# eFingernailAllComponents.net
KiCad netlist of a schematic drawn in EAGLE
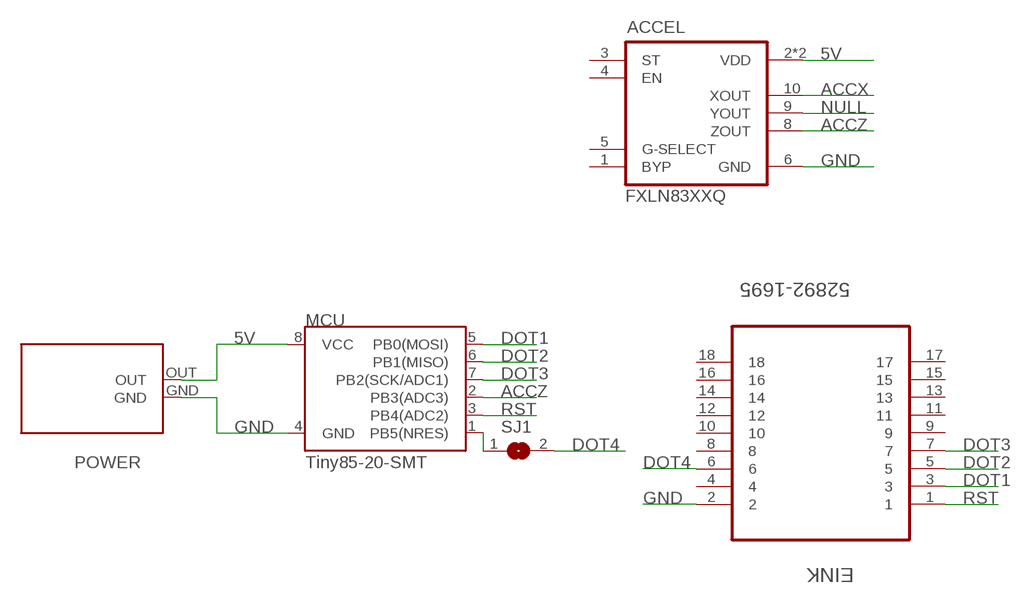
[diagram p0: schematic, sheet 1]

(export (version "E")
  (design (tool "Eeschema 10.0.6"))
  (components
    (comp (ref "ACCEL")
      (value "FXLN83XXQ")
      (footprint "eagle-import:QFN12-3X3")
      (libsource (lib "eagle-import") (part "FXLN83XXQ"))
    )
    (comp (ref "EINK")
      (value "52892-1695")
      (footprint "eagle-import:MOLEX_52892-1695")
      (libsource (lib "eagle-import") (part "52892-1695"))
    )
    (comp (ref "MCU")
      (value "Tiny85-20-SMT")
      (footprint "eagle-import:SO08-EIAJ")
      (libsource (lib "eagle-import") (part "ATTINY45TINY85-20-SMT"))
    )
    (comp (ref "POWER")
      (value "P9027LP-R")
      (footprint "eagle-import:P9027LP-R")
      (libsource (lib "eagle-import") (part "P9027LP-R"))
    )
    (comp (ref "SJ1")
      (value "SOLDERJUMPER")
      (footprint "eagle-import:SOLDERJUMPER_ARROW_NOPASTE")
      (libsource (lib "eagle-import") (part "SOLDERJUMPER"))
    )
  )
  (nets
    (net (code "1") (name "/5V") (class "Default")
      (node (ref "ACCEL") (pin "2") (pinfunction "VDD_2") (pintype "power_in"))
      (node (ref "ACCEL") (pin "7") (pinfunction "VDD_7") (pintype "power_in"))
      (node (ref "MCU") (pin "8") (pinfunction "VCC_8") (pintype "bidirectional"))
      (node (ref "POWER") (pin "OUT") (pinfunction "OUT_OUT") (pintype "power_in"))
    )
    (net (code "2") (name "/ACCX") (class "Default")
      (node (ref "ACCEL") (pin "10") (pinfunction "XOUT_10") (pintype "output"))
    )
    (net (code "3") (name "/ACCZ") (class "Default")
      (node (ref "ACCEL") (pin "8") (pinfunction "ZOUT_8") (pintype "output"))
      (node (ref "MCU") (pin "2") (pinfunction "PB3(ADC3)_2") (pintype "bidirectional"))
    )
    (net (code "4") (name "/DOT1") (class "Default")
      (node (ref "EINK") (pin "3") (pinfunction "3_3") (pintype "passive"))
      (node (ref "MCU") (pin "5") (pinfunction "PB0(MOSI)_5") (pintype "bidirectional"))
    )
    (net (code "5") (name "/DOT2") (class "Default")
      (node (ref "EINK") (pin "5") (pinfunction "5_5") (pintype "passive"))
      (node (ref "MCU") (pin "6") (pinfunction "PB1(MISO)_6") (pintype "bidirectional"))
    )
    (net (code "6") (name "/DOT3") (class "Default")
      (node (ref "EINK") (pin "7") (pinfunction "7_7") (pintype "passive"))
      (node (ref "MCU") (pin "7") (pinfunction "PB2(SCK/ADC1)_7") (pintype "bidirectional"))
    )
    (net (code "7") (name "/DOT4") (class "Default")
      (node (ref "EINK") (pin "6") (pinfunction "6_6") (pintype "passive"))
      (node (ref "SJ1") (pin "2") (pinfunction "2_2") (pintype "passive"))
    )
    (net (code "8") (name "/GND") (class "Default")
      (node (ref "ACCEL") (pin "6") (pinfunction "GND_6") (pintype "power_in"))
      (node (ref "EINK") (pin "2") (pinfunction "2_2") (pintype "passive"))
      (node (ref "MCU") (pin "4") (pinfunction "GND_4") (pintype "bidirectional"))
      (node (ref "POWER") (pin "GND") (pinfunction "GND_GND") (pintype "power_in"))
    )
    (net (code "9") (name "/NULL") (class "Default")
      (node (ref "ACCEL") (pin "9") (pinfunction "YOUT_9") (pintype "output"))
    )
    (net (code "10") (name "/RST") (class "Default")
      (node (ref "EINK") (pin "1") (pinfunction "1_1") (pintype "passive"))
      (node (ref "MCU") (pin "3") (pinfunction "PB4(ADC2)_3") (pintype "bidirectional"))
    )
    (net (code "11") (name "Net-(MCU-PB5(NRES))") (class "Default")
      (node (ref "MCU") (pin "1") (pinfunction "PB5(NRES)_1") (pintype "bidirectional"))
      (node (ref "SJ1") (pin "1") (pinfunction "1_1") (pintype "passive"))
    )
    (net (code "12") (name "unconnected-(ACCEL-BYP-Pad1)") (class "Default")
      (node (ref "ACCEL") (pin "1") (pinfunction "BYP_1") (pintype "bidirectional"))
    )
    (net (code "13") (name "unconnected-(ACCEL-EN-Pad4)") (class "Default")
      (node (ref "ACCEL") (pin "4") (pinfunction "EN_4") (pintype "bidirectional"))
    )
    (net (code "14") (name "unconnected-(ACCEL-G-SELECT-Pad5)") (class "Default")
      (node (ref "ACCEL") (pin "5") (pinfunction "G-SELECT_5") (pintype "bidirectional"))
    )
    (net (code "15") (name "unconnected-(ACCEL-ST-Pad3)") (class "Default")
      (node (ref "ACCEL") (pin "3") (pinfunction "ST_3") (pintype "bidirectional"))
    )
    (net (code "16") (name "unconnected-(EINK-Pad4)") (class "Default")
      (node (ref "EINK") (pin "4") (pinfunction "4_4") (pintype "passive"))
    )
    (net (code "17") (name "unconnected-(EINK-Pad8)") (class "Default")
      (node (ref "EINK") (pin "8") (pinfunction "8_8") (pintype "passive"))
    )
    (net (code "18") (name "unconnected-(EINK-Pad9)") (class "Default")
      (node (ref "EINK") (pin "9") (pinfunction "9_9") (pintype "passive"))
    )
    (net (code "19") (name "unconnected-(EINK-Pad10)") (class "Default")
      (node (ref "EINK") (pin "10") (pinfunction "10_10") (pintype "passive"))
    )
    (net (code "20") (name "unconnected-(EINK-Pad11)") (class "Default")
      (node (ref "EINK") (pin "11") (pinfunction "11_11") (pintype "passive"))
    )
    (net (code "21") (name "unconnected-(EINK-Pad12)") (class "Default")
      (node (ref "EINK") (pin "12") (pinfunction "12_12") (pintype "passive"))
    )
    (net (code "22") (name "unconnected-(EINK-Pad13)") (class "Default")
      (node (ref "EINK") (pin "13") (pinfunction "13_13") (pintype "passive"))
    )
    (net (code "23") (name "unconnected-(EINK-Pad14)") (class "Default")
      (node (ref "EINK") (pin "14") (pinfunction "14_14") (pintype "passive"))
    )
    (net (code "24") (name "unconnected-(EINK-Pad15)") (class "Default")
      (node (ref "EINK") (pin "15") (pinfunction "15_15") (pintype "passive"))
    )
    (net (code "25") (name "unconnected-(EINK-Pad16)") (class "Default")
      (node (ref "EINK") (pin "16") (pinfunction "16_16") (pintype "passive"))
    )
    (net (code "26") (name "unconnected-(EINK-Pad17)") (class "Default")
      (node (ref "EINK") (pin "17") (pinfunction "17_17") (pintype "passive"))
    )
    (net (code "27") (name "unconnected-(EINK-Pad18)") (class "Default")
      (node (ref "EINK") (pin "18") (pinfunction "18_18") (pintype "passive"))
    )
  )
)
